# 3channel_thermocouple.net
KiCad netlist of a schematic drawn in EAGLE
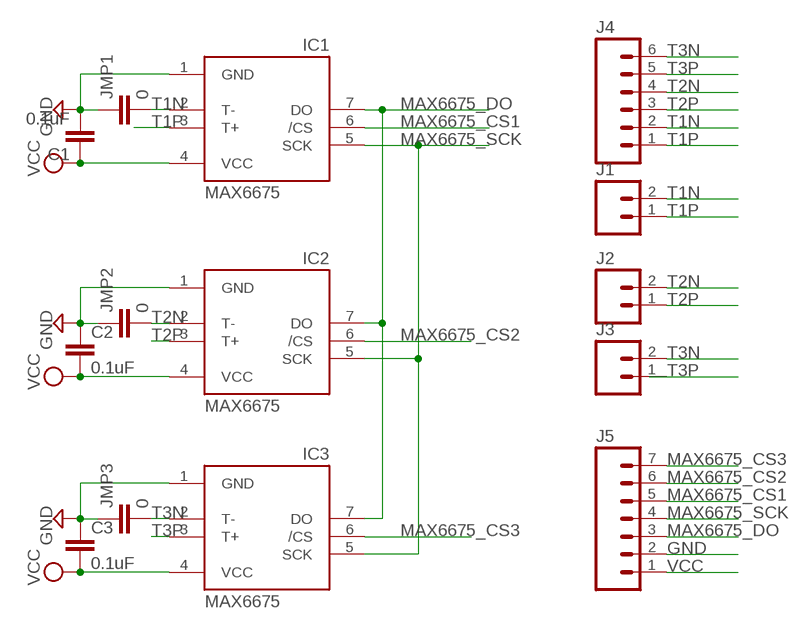
[diagram p0: schematic, sheet 1]

(export (version "E")
  (design (tool "Eeschema 10.0.6"))
  (components
    (comp (ref "C1")
      (value "0.1uF")
      (footprint "eagle-import:0603-CAP")
      (libsource (lib "eagle-import") (part "0.1UF-25V(+80/-20%)(0603)"))
    )
    (comp (ref "C2")
      (value "0.1uF")
      (footprint "eagle-import:0603-CAP")
      (libsource (lib "eagle-import") (part "0.1UF-25V(+80/-20%)(0603)"))
    )
    (comp (ref "C3")
      (value "0.1uF")
      (footprint "eagle-import:0603-CAP")
      (libsource (lib "eagle-import") (part "0.1UF-25V(+80/-20%)(0603)"))
    )
    (comp (ref "IC1")
      (value "MAX6675")
      (footprint "eagle-import:SO08")
      (libsource (lib "eagle-import") (part "MAX6675"))
    )
    (comp (ref "IC2")
      (value "MAX6675")
      (footprint "eagle-import:SO08")
      (libsource (lib "eagle-import") (part "MAX6675"))
    )
    (comp (ref "IC3")
      (value "MAX6675")
      (footprint "eagle-import:SO08")
      (libsource (lib "eagle-import") (part "MAX6675"))
    )
    (comp (ref "J1")
      (value "M025MM")
      (footprint "eagle-import:SCREWTERMINAL-5MM-2")
      (libsource (lib "eagle-import") (part "M025MM"))
    )
    (comp (ref "J2")
      (value "M025MM")
      (footprint "eagle-import:SCREWTERMINAL-5MM-2")
      (libsource (lib "eagle-import") (part "M025MM"))
    )
    (comp (ref "J3")
      (value "M025MM")
      (footprint "eagle-import:SCREWTERMINAL-5MM-2")
      (libsource (lib "eagle-import") (part "M025MM"))
    )
    (comp (ref "J4")
      (value "M06")
      (footprint "eagle-import:1X6-XH-JST-S6B-RIGHTANGLE")
      (libsource (lib "eagle-import") (part "M06"))
    )
    (comp (ref "J5")
      (value "M07")
      (footprint "eagle-import:1X07")
      (libsource (lib "eagle-import") (part "M07"))
    )
    (comp (ref "JMP1")
      (value "0")
      (footprint "eagle-import:0603-CAP")
      (libsource (lib "eagle-import") (part "0.1UF-25V(+80/-20%)(0603)"))
    )
    (comp (ref "JMP2")
      (value "0")
      (footprint "eagle-import:0603-CAP")
      (libsource (lib "eagle-import") (part "0.1UF-25V(+80/-20%)(0603)"))
    )
    (comp (ref "JMP3")
      (value "0")
      (footprint "eagle-import:0603-CAP")
      (libsource (lib "eagle-import") (part "0.1UF-25V(+80/-20%)(0603)"))
    )
  )
  (nets
    (net (code "1") (name "/MAX6675_CS1") (class "Default")
      (node (ref "IC1") (pin "6") (pinfunction "/CS_6") (pintype "input"))
      (node (ref "J5") (pin "5") (pinfunction "5_5") (pintype "passive"))
    )
    (net (code "2") (name "/MAX6675_CS2") (class "Default")
      (node (ref "IC2") (pin "6") (pinfunction "/CS_6") (pintype "input"))
      (node (ref "J5") (pin "6") (pinfunction "6_6") (pintype "passive"))
    )
    (net (code "3") (name "/MAX6675_CS3") (class "Default")
      (node (ref "IC3") (pin "6") (pinfunction "/CS_6") (pintype "input"))
      (node (ref "J5") (pin "7") (pinfunction "7_7") (pintype "passive"))
    )
    (net (code "4") (name "/MAX6675_DO") (class "Default")
      (node (ref "IC1") (pin "7") (pinfunction "DO_7") (pintype "output"))
      (node (ref "IC2") (pin "7") (pinfunction "DO_7") (pintype "output"))
      (node (ref "IC3") (pin "7") (pinfunction "DO_7") (pintype "output"))
      (node (ref "J5") (pin "3") (pinfunction "3_3") (pintype "passive"))
    )
    (net (code "5") (name "/MAX6675_SCK") (class "Default")
      (node (ref "IC1") (pin "5") (pinfunction "SCK_5") (pintype "input"))
      (node (ref "IC2") (pin "5") (pinfunction "SCK_5") (pintype "input"))
      (node (ref "IC3") (pin "5") (pinfunction "SCK_5") (pintype "input"))
      (node (ref "J5") (pin "4") (pinfunction "4_4") (pintype "passive"))
    )
    (net (code "6") (name "/T1N") (class "Default")
      (node (ref "IC1") (pin "2") (pinfunction "T-_2") (pintype "input"))
      (node (ref "J1") (pin "2") (pinfunction "2_2") (pintype "passive"))
      (node (ref "J4") (pin "2") (pinfunction "2_2") (pintype "passive"))
      (node (ref "JMP1") (pin "2") (pinfunction "2_2") (pintype "passive"))
    )
    (net (code "7") (name "/T1P") (class "Default")
      (node (ref "IC1") (pin "3") (pinfunction "T+_3") (pintype "input"))
      (node (ref "J1") (pin "1") (pinfunction "1_1") (pintype "passive"))
      (node (ref "J4") (pin "1") (pinfunction "1_1") (pintype "passive"))
    )
    (net (code "8") (name "/T2N") (class "Default")
      (node (ref "IC2") (pin "2") (pinfunction "T-_2") (pintype "input"))
      (node (ref "J2") (pin "2") (pinfunction "2_2") (pintype "passive"))
      (node (ref "J4") (pin "4") (pinfunction "4_4") (pintype "passive"))
      (node (ref "JMP2") (pin "2") (pinfunction "2_2") (pintype "passive"))
    )
    (net (code "9") (name "/T2P") (class "Default")
      (node (ref "IC2") (pin "3") (pinfunction "T+_3") (pintype "input"))
      (node (ref "J2") (pin "1") (pinfunction "1_1") (pintype "passive"))
      (node (ref "J4") (pin "3") (pinfunction "3_3") (pintype "passive"))
    )
    (net (code "10") (name "/T3N") (class "Default")
      (node (ref "IC3") (pin "2") (pinfunction "T-_2") (pintype "input"))
      (node (ref "J3") (pin "2") (pinfunction "2_2") (pintype "passive"))
      (node (ref "J4") (pin "6") (pinfunction "6_6") (pintype "passive"))
      (node (ref "JMP3") (pin "2") (pinfunction "2_2") (pintype "passive"))
    )
    (net (code "11") (name "/T3P") (class "Default")
      (node (ref "IC3") (pin "3") (pinfunction "T+_3") (pintype "input"))
      (node (ref "J3") (pin "1") (pinfunction "1_1") (pintype "passive"))
      (node (ref "J4") (pin "5") (pinfunction "5_5") (pintype "passive"))
    )
    (net (code "12") (name "GND") (class "Default")
      (node (ref "C1") (pin "2") (pinfunction "2_2") (pintype "passive"))
      (node (ref "C2") (pin "1") (pinfunction "1_1") (pintype "passive"))
      (node (ref "C3") (pin "1") (pinfunction "1_1") (pintype "passive"))
      (node (ref "IC1") (pin "1") (pinfunction "GND_1") (pintype "power_in"))
      (node (ref "IC2") (pin "1") (pinfunction "GND_1") (pintype "power_in"))
      (node (ref "IC3") (pin "1") (pinfunction "GND_1") (pintype "power_in"))
      (node (ref "J5") (pin "2") (pinfunction "2_2") (pintype "passive"))
      (node (ref "JMP1") (pin "1") (pinfunction "1_1") (pintype "passive"))
      (node (ref "JMP2") (pin "1") (pinfunction "1_1") (pintype "passive"))
      (node (ref "JMP3") (pin "1") (pinfunction "1_1") (pintype "passive"))
    )
    (net (code "13") (name "VCC") (class "Default")
      (node (ref "C1") (pin "1") (pinfunction "1_1") (pintype "passive"))
      (node (ref "C2") (pin "2") (pinfunction "2_2") (pintype "passive"))
      (node (ref "C3") (pin "2") (pinfunction "2_2") (pintype "passive"))
      (node (ref "IC1") (pin "4") (pinfunction "VCC_4") (pintype "power_in"))
      (node (ref "IC2") (pin "4") (pinfunction "VCC_4") (pintype "power_in"))
      (node (ref "IC3") (pin "4") (pinfunction "VCC_4") (pintype "power_in"))
      (node (ref "J5") (pin "1") (pinfunction "1_1") (pintype "passive"))
    )
  )
)
